# sc_v0.net
KiCad netlist of a schematic drawn in EAGLE
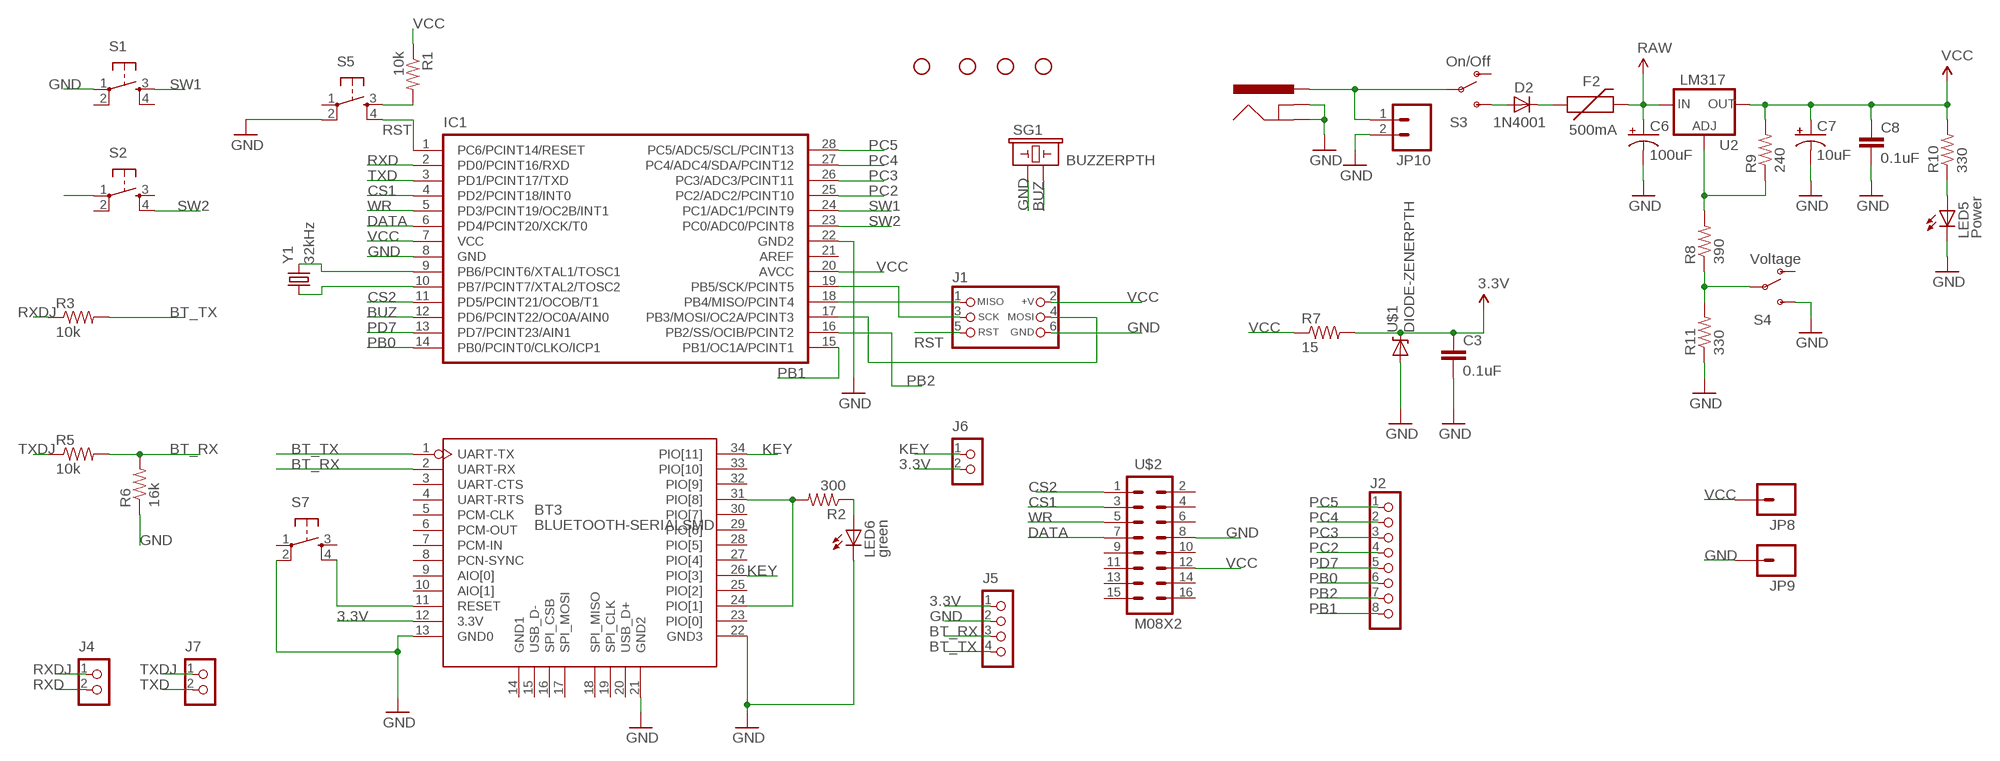
[diagram p0: schematic, sheet 1]

(export (version "E")
  (design (tool "Eeschema 10.0.6"))
  (components
    (comp (ref "BT3")
      (value "BLUETOOTH-SERIALSMD")
      (footprint "eagle-import:SERIAL_BLUETEETH")
      (libsource (lib "eagle-import") (part "BLUETOOTH-SERIALSMD"))
    )
    (comp (ref "C3")
      (value "0.1uF")
      (footprint "eagle-import:CAP-PTH-SMALL2")
      (libsource (lib "eagle-import") (part "CAPPTH2"))
    )
    (comp (ref "C6")
      (value "100uF")
      (footprint "eagle-import:CPOL-RADIAL-100UF-25V")
      (libsource (lib "eagle-import") (part "CAP_POLPTH1"))
    )
    (comp (ref "C7")
      (value "10uF")
      (footprint "eagle-import:CPOL-RADIAL-10UF-25V")
      (libsource (lib "eagle-import") (part "CAP_POLPTH2"))
    )
    (comp (ref "C8")
      (value "0.1uF")
      (footprint "eagle-import:CAP-PTH-SMALL2")
      (libsource (lib "eagle-import") (part "CAPPTH2"))
    )
    (comp (ref "D2")
      (value "1N4001")
      (footprint "eagle-import:DIODE-0.4")
      (libsource (lib "eagle-import") (part "DIODEPTH"))
    )
    (comp (ref "F2")
      (value "500mA")
      (footprint "eagle-import:PTC")
      (libsource (lib "eagle-import") (part "PTCPTH"))
    )
    (comp (ref "IC1")
      (value "IC_UC_ATMEGA328PDIL")
      (footprint "eagle-import:DIL28-N")
      (libsource (lib "eagle-import") (part "IC_UC_ATMEGA328PDIL"))
    )
    (comp (ref "J1")
      (value "CON_HEADER_PRG_AVR_ICSP")
      (footprint "eagle-import:HEADER_PRG_2X03")
      (libsource (lib "eagle-import") (part "CON_HEADER_PRG_AVR_ICSP"))
    )
    (comp (ref "J2")
      (value "CON_HEADER_1X08-PTH")
      (footprint "eagle-import:M1X8")
      (libsource (lib "eagle-import") (part "CON_HEADER_1X08-PTH"))
    )
    (comp (ref "J3")
      (value "POWER_JACKPTH")
      (footprint "eagle-import:POWER_JACK_PTH")
      (libsource (lib "eagle-import") (part "POWER_JACKPTH"))
    )
    (comp (ref "J4")
      (value "CON_HEADER_1X02-PTH")
      (footprint "eagle-import:M1X2")
      (libsource (lib "eagle-import") (part "CON_HEADER_1X02-PTH"))
    )
    (comp (ref "J5")
      (value "CON_HEADER_1X04")
      (footprint "eagle-import:M1X4")
      (libsource (lib "eagle-import") (part "CON_HEADER_1X04"))
    )
    (comp (ref "J6")
      (value "CON_HEADER_1X02-PTH")
      (footprint "eagle-import:M1X2")
      (libsource (lib "eagle-import") (part "CON_HEADER_1X02-PTH"))
    )
    (comp (ref "J7")
      (value "CON_HEADER_1X02-PTH")
      (footprint "eagle-import:M1X2")
      (libsource (lib "eagle-import") (part "CON_HEADER_1X02-PTH"))
    )
    (comp (ref "JP1")
      (value "STAND-OFF")
      (footprint "eagle-import:STAND-OFF")
      (libsource (lib "eagle-import") (part "STAND-OFF"))
    )
    (comp (ref "JP2")
      (value "STAND-OFF")
      (footprint "eagle-import:STAND-OFF")
      (libsource (lib "eagle-import") (part "STAND-OFF"))
    )
    (comp (ref "JP3")
      (value "STAND-OFF")
      (footprint "eagle-import:STAND-OFF")
      (libsource (lib "eagle-import") (part "STAND-OFF"))
    )
    (comp (ref "JP4")
      (value "STAND-OFF")
      (footprint "eagle-import:STAND-OFF")
      (libsource (lib "eagle-import") (part "STAND-OFF"))
    )
    (comp (ref "JP8")
      (value "M01PTH")
      (footprint "eagle-import:1X01")
      (libsource (lib "eagle-import") (part "M01PTH"))
    )
    (comp (ref "JP9")
      (value "M01PTH")
      (footprint "eagle-import:1X01")
      (libsource (lib "eagle-import") (part "M01PTH"))
    )
    (comp (ref "JP10")
      (value "M02PTH")
      (footprint "eagle-import:1X02")
      (libsource (lib "eagle-import") (part "M02PTH"))
    )
    (comp (ref "LED5")
      (value "Power")
      (footprint "eagle-import:LED5MM")
      (libsource (lib "eagle-import") (part "SparkFun-Nate_LED5MM"))
    )
    (comp (ref "LED6")
      (value "green")
      (footprint "eagle-import:LED3MM")
      (libsource (lib "eagle-import") (part "LED3MM"))
    )
    (comp (ref "R1")
      (value "10k")
      (footprint "eagle-import:AXIAL-0.3")
      (libsource (lib "eagle-import") (part "RESISTORAXIAL-0.3"))
    )
    (comp (ref "R2")
      (value "300")
      (footprint "eagle-import:AXIAL-0.3")
      (libsource (lib "eagle-import") (part "RESISTORAXIAL-0.3"))
    )
    (comp (ref "R3")
      (value "10k")
      (footprint "eagle-import:AXIAL-0.3")
      (libsource (lib "eagle-import") (part "RESISTORAXIAL-0.3"))
    )
    (comp (ref "R5")
      (value "10k")
      (footprint "eagle-import:AXIAL-0.3")
      (libsource (lib "eagle-import") (part "RESISTORAXIAL-0.3"))
    )
    (comp (ref "R6")
      (value "16k")
      (footprint "eagle-import:AXIAL-0.3")
      (libsource (lib "eagle-import") (part "RESISTORAXIAL-0.3"))
    )
    (comp (ref "R7")
      (value "15")
      (footprint "eagle-import:AXIAL-0.3")
      (libsource (lib "eagle-import") (part "RESISTORAXIAL-0.3"))
    )
    (comp (ref "R8")
      (value "390")
      (footprint "eagle-import:AXIAL-0.3")
      (libsource (lib "eagle-import") (part "RESISTORAXIAL-0.3"))
    )
    (comp (ref "R9")
      (value "240")
      (footprint "eagle-import:AXIAL-0.3")
      (libsource (lib "eagle-import") (part "RESISTORAXIAL-0.3"))
    )
    (comp (ref "R10")
      (value "330")
      (footprint "eagle-import:AXIAL-0.3")
      (libsource (lib "eagle-import") (part "RESISTORAXIAL-0.3"))
    )
    (comp (ref "R11")
      (value "330")
      (footprint "eagle-import:AXIAL-0.3")
      (libsource (lib "eagle-import") (part "RESISTORAXIAL-0.3"))
    )
    (comp (ref "S1")
      (value "TAC_SWITCHPTH")
      (footprint "eagle-import:TACTILE-PTH")
      (libsource (lib "eagle-import") (part "TAC_SWITCHPTH"))
    )
    (comp (ref "S2")
      (value "TAC_SWITCHPTH")
      (footprint "eagle-import:TACTILE-PTH")
      (libsource (lib "eagle-import") (part "TAC_SWITCHPTH"))
    )
    (comp (ref "S3")
      (value "On/Off")
      (footprint "eagle-import:SWITCH-SPST")
      (libsource (lib "eagle-import") (part "SWITCH-SPSTPTH"))
    )
    (comp (ref "S4")
      (value "Voltage")
      (footprint "eagle-import:SWITCH-SPST")
      (libsource (lib "eagle-import") (part "SWITCH-SPSTPTH"))
    )
    (comp (ref "S5")
      (value "TAC_SWITCHPTH")
      (footprint "eagle-import:TACTILE-PTH")
      (libsource (lib "eagle-import") (part "TAC_SWITCHPTH"))
    )
    (comp (ref "S7")
      (value "TAC_SWITCHPTH")
      (footprint "eagle-import:TACTILE-PTH")
      (libsource (lib "eagle-import") (part "TAC_SWITCHPTH"))
    )
    (comp (ref "SG1")
      (value "BUZZERPTH")
      (footprint "eagle-import:BUZZER-12MM")
      (libsource (lib "eagle-import") (part "BUZZERPTH"))
    )
    (comp (ref "U$1")
      (value "DIODE-ZENERPTH")
      (footprint "eagle-import:DIODE-ZENER")
      (libsource (lib "eagle-import") (part "DIODE-ZENERPTH"))
    )
    (comp (ref "U$2")
      (value "M08X2")
      (footprint "eagle-import:2X8")
      (libsource (lib "eagle-import") (part "M08X2"))
    )
    (comp (ref "U2")
      (value "LM317")
      (footprint "eagle-import:TO220-ADJ")
      (libsource (lib "eagle-import") (part "V_REG_317SINK"))
    )
    (comp (ref "Y1")
      (value "32kHz")
      (footprint "eagle-import:TC38H")
      (libsource (lib "eagle-import") (part "CRYSTALTC38H"))
    )
  )
  (nets
    (net (code "1") (name "/BT_RX") (class "Default")
      (node (ref "BT3") (pin "2") (pinfunction "UART-RX_2") (pintype "bidirectional"))
      (node (ref "J5") (pin "3") (pinfunction "3_3") (pintype "bidirectional"))
      (node (ref "R5") (pin "P$2") (pinfunction "2_P$2") (pintype "passive"))
      (node (ref "R6") (pin "P$2") (pinfunction "2_P$2") (pintype "passive"))
    )
    (net (code "2") (name "/BT_TX") (class "Default")
      (node (ref "BT3") (pin "1") (pinfunction "UART-TX_1") (pintype "bidirectional"))
      (node (ref "J5") (pin "4") (pinfunction "4_4") (pintype "bidirectional"))
      (node (ref "R3") (pin "P$2") (pinfunction "2_P$2") (pintype "passive"))
    )
    (net (code "3") (name "/BUZ") (class "Default")
      (node (ref "IC1") (pin "12") (pinfunction "PD6/PCINT22/OC0A/AIN0_12") (pintype "bidirectional"))
      (node (ref "SG1") (pin "-") (pinfunction "2_-") (pintype "passive"))
    )
    (net (code "4") (name "/CS1") (class "Default")
      (node (ref "IC1") (pin "4") (pinfunction "PD2/PCINT18/INT0_4") (pintype "bidirectional"))
      (node (ref "U$2") (pin "3") (pinfunction "3_3") (pintype "passive"))
    )
    (net (code "5") (name "/CS2") (class "Default")
      (node (ref "IC1") (pin "11") (pinfunction "PD5/PCINT21/OCOB/T1_11") (pintype "bidirectional"))
      (node (ref "U$2") (pin "1") (pinfunction "1_1") (pintype "passive"))
    )
    (net (code "6") (name "/DATA") (class "Default")
      (node (ref "IC1") (pin "6") (pinfunction "PD4/PCINT20/XCK/T0_6") (pintype "bidirectional"))
      (node (ref "U$2") (pin "7") (pinfunction "7_7") (pintype "passive"))
    )
    (net (code "7") (name "/KEY") (class "Default")
      (node (ref "BT3") (pin "26") (pinfunction "PIO[3]_26") (pintype "bidirectional"))
      (node (ref "BT3") (pin "34") (pinfunction "PIO[11]_34") (pintype "bidirectional"))
      (node (ref "J6") (pin "1") (pinfunction "1_1") (pintype "passive"))
    )
    (net (code "8") (name "/PB0") (class "Default")
      (node (ref "IC1") (pin "14") (pinfunction "PB0/PCINT0/CLKO/ICP1_14") (pintype "bidirectional"))
      (node (ref "J2") (pin "6") (pinfunction "6_6") (pintype "passive"))
    )
    (net (code "9") (name "/PB1") (class "Default")
      (node (ref "IC1") (pin "15") (pinfunction "PB1/OC1A/PCINT1_15") (pintype "bidirectional"))
      (node (ref "J2") (pin "8") (pinfunction "8_8") (pintype "passive"))
    )
    (net (code "10") (name "/PB2") (class "Default")
      (node (ref "IC1") (pin "16") (pinfunction "PB2/SS/OCIB/PCINT2_16") (pintype "bidirectional"))
      (node (ref "J2") (pin "7") (pinfunction "7_7") (pintype "passive"))
    )
    (net (code "11") (name "/PC2") (class "Default")
      (node (ref "IC1") (pin "25") (pinfunction "PC2/ADC2/PCINT10_25") (pintype "bidirectional"))
      (node (ref "J2") (pin "4") (pinfunction "4_4") (pintype "passive"))
    )
    (net (code "12") (name "/PC3") (class "Default")
      (node (ref "IC1") (pin "26") (pinfunction "PC3/ADC3/PCINT11_26") (pintype "bidirectional"))
      (node (ref "J2") (pin "3") (pinfunction "3_3") (pintype "passive"))
    )
    (net (code "13") (name "/PC4") (class "Default")
      (node (ref "IC1") (pin "27") (pinfunction "PC4/ADC4/SDA/PCINT12_27") (pintype "bidirectional"))
      (node (ref "J2") (pin "2") (pinfunction "2_2") (pintype "passive"))
    )
    (net (code "14") (name "/PC5") (class "Default")
      (node (ref "IC1") (pin "28") (pinfunction "PC5/ADC5/SCL/PCINT13_28") (pintype "bidirectional"))
      (node (ref "J2") (pin "1") (pinfunction "1_1") (pintype "passive"))
    )
    (net (code "15") (name "/PD7") (class "Default")
      (node (ref "IC1") (pin "13") (pinfunction "PD7/PCINT23/AIN1_13") (pintype "bidirectional"))
      (node (ref "J2") (pin "5") (pinfunction "5_5") (pintype "passive"))
    )
    (net (code "16") (name "/RST") (class "Default")
      (node (ref "IC1") (pin "1") (pinfunction "PC6/PCINT14/RESET_1") (pintype "bidirectional"))
      (node (ref "J1") (pin "5") (pinfunction "RST_5") (pintype "passive"))
      (node (ref "S5") (pin "4") (pinfunction "4_4") (pintype "passive"))
    )
    (net (code "17") (name "/RXD") (class "Default")
      (node (ref "IC1") (pin "2") (pinfunction "PD0/PCINT16/RXD_2") (pintype "bidirectional"))
      (node (ref "J4") (pin "2") (pinfunction "2_2") (pintype "passive"))
    )
    (net (code "18") (name "/RXDJ") (class "Default")
      (node (ref "J4") (pin "1") (pinfunction "1_1") (pintype "passive"))
      (node (ref "R3") (pin "P$1") (pinfunction "1_P$1") (pintype "passive"))
    )
    (net (code "19") (name "/SW1") (class "Default")
      (node (ref "IC1") (pin "24") (pinfunction "PC1/ADC1/PCINT9_24") (pintype "bidirectional"))
      (node (ref "S1") (pin "3") (pinfunction "3_3") (pintype "passive"))
    )
    (net (code "20") (name "/SW2") (class "Default")
      (node (ref "IC1") (pin "23") (pinfunction "PC0/ADC0/PCINT8_23") (pintype "bidirectional"))
      (node (ref "S2") (pin "4") (pinfunction "4_4") (pintype "passive"))
    )
    (net (code "21") (name "/TXD") (class "Default")
      (node (ref "IC1") (pin "3") (pinfunction "PD1/PCINT17/TXD_3") (pintype "bidirectional"))
      (node (ref "J7") (pin "2") (pinfunction "2_2") (pintype "passive"))
    )
    (net (code "22") (name "/TXDJ") (class "Default")
      (node (ref "J7") (pin "1") (pinfunction "1_1") (pintype "passive"))
      (node (ref "R5") (pin "P$1") (pinfunction "1_P$1") (pintype "passive"))
    )
    (net (code "23") (name "/WR") (class "Default")
      (node (ref "IC1") (pin "5") (pinfunction "PD3/PCINT19/OC2B/INT1_5") (pintype "bidirectional"))
      (node (ref "U$2") (pin "5") (pinfunction "5_5") (pintype "passive"))
    )
    (net (code "24") (name "3.3V") (class "Default")
      (node (ref "BT3") (pin "12") (pinfunction "3.3V_12") (pintype "bidirectional"))
      (node (ref "C3") (pin "1") (pinfunction "1_1") (pintype "passive"))
      (node (ref "J5") (pin "1") (pinfunction "1_1") (pintype "bidirectional"))
      (node (ref "J6") (pin "2") (pinfunction "2_2") (pintype "passive"))
      (node (ref "R7") (pin "P$2") (pinfunction "2_P$2") (pintype "passive"))
      (node (ref "U$1") (pin "P$1") (pinfunction "C_P$1") (pintype "passive"))
    )
    (net (code "25") (name "GND") (class "Default")
      (node (ref "BT3") (pin "13") (pinfunction "GND0_13") (pintype "bidirectional"))
      (node (ref "BT3") (pin "21") (pinfunction "GND2_21") (pintype "bidirectional"))
      (node (ref "BT3") (pin "22") (pinfunction "GND3_22") (pintype "bidirectional"))
      (node (ref "C3") (pin "2") (pinfunction "2_2") (pintype "passive"))
      (node (ref "C6") (pin "2") (pinfunction "-_2") (pintype "passive"))
      (node (ref "C7") (pin "2") (pinfunction "-_2") (pintype "passive"))
      (node (ref "C8") (pin "2") (pinfunction "2_2") (pintype "passive"))
      (node (ref "IC1") (pin "22") (pinfunction "GND2_22") (pintype "bidirectional"))
      (node (ref "IC1") (pin "8") (pinfunction "GND_8") (pintype "bidirectional"))
      (node (ref "J1") (pin "6") (pinfunction "GND_6") (pintype "passive"))
      (node (ref "J3") (pin "GND") (pinfunction "GND_GND") (pintype "bidirectional"))
      (node (ref "J3") (pin "GNDBREAK") (pinfunction "GNDBREAK_GNDBREAK") (pintype "bidirectional"))
      (node (ref "J5") (pin "2") (pinfunction "2_2") (pintype "bidirectional"))
      (node (ref "JP10") (pin "2") (pinfunction "2_2") (pintype "passive"))
      (node (ref "JP9") (pin "1") (pinfunction "1_1") (pintype "passive"))
      (node (ref "LED5") (pin "K") (pinfunction "C_K") (pintype "passive"))
      (node (ref "LED6") (pin "K") (pinfunction "C_K") (pintype "passive"))
      (node (ref "R11") (pin "P$1") (pinfunction "1_P$1") (pintype "passive"))
      (node (ref "R6") (pin "P$1") (pinfunction "1_P$1") (pintype "passive"))
      (node (ref "S1") (pin "1") (pinfunction "1_1") (pintype "passive"))
      (node (ref "S2") (pin "1") (pinfunction "1_1") (pintype "passive"))
      (node (ref "S4") (pin "3") (pinfunction "S_3") (pintype "passive"))
      (node (ref "S5") (pin "2") (pinfunction "2_2") (pintype "passive"))
      (node (ref "S7") (pin "2") (pinfunction "2_2") (pintype "passive"))
      (node (ref "SG1") (pin "+") (pinfunction "1_+") (pintype "passive"))
      (node (ref "U$1") (pin "P$2") (pinfunction "A_P$2") (pintype "passive"))
      (node (ref "U$2") (pin "8") (pinfunction "8_8") (pintype "passive"))
    )
    (net (code "26") (name "Net-(BT3-PIO[1])") (class "Default")
      (node (ref "BT3") (pin "24") (pinfunction "PIO[1]_24") (pintype "bidirectional"))
      (node (ref "BT3") (pin "31") (pinfunction "PIO[8]_31") (pintype "bidirectional"))
      (node (ref "R2") (pin "P$2") (pinfunction "2_P$2") (pintype "passive"))
    )
    (net (code "27") (name "Net-(BT3-RESET)") (class "Default")
      (node (ref "BT3") (pin "11") (pinfunction "RESET_11") (pintype "bidirectional"))
      (node (ref "S7") (pin "4") (pinfunction "4_4") (pintype "passive"))
    )
    (net (code "28") (name "Net-(F2-1)") (class "Default")
      (node (ref "D2") (pin "C") (pinfunction "C_C") (pintype "passive"))
      (node (ref "F2") (pin "P$1") (pinfunction "1_P$1") (pintype "bidirectional"))
    )
    (net (code "29") (name "Net-(IC1-PB3{slash}MOSI{slash}OC2A{slash}PCINT3)") (class "Default")
      (node (ref "IC1") (pin "17") (pinfunction "PB3/MOSI/OC2A/PCINT3_17") (pintype "bidirectional"))
      (node (ref "J1") (pin "4") (pinfunction "MOSI_4") (pintype "passive"))
    )
    (net (code "30") (name "Net-(IC1-PB4{slash}MISO{slash}PCINT4)") (class "Default")
      (node (ref "IC1") (pin "18") (pinfunction "PB4/MISO/PCINT4_18") (pintype "bidirectional"))
      (node (ref "J1") (pin "1") (pinfunction "MISO_1") (pintype "passive"))
    )
    (net (code "31") (name "Net-(IC1-PB5{slash}SCK{slash}PCINT5)") (class "Default")
      (node (ref "IC1") (pin "19") (pinfunction "PB5/SCK/PCINT5_19") (pintype "bidirectional"))
      (node (ref "J1") (pin "3") (pinfunction "SCK_3") (pintype "passive"))
    )
    (net (code "32") (name "Net-(IC1-PB6{slash}PCINT6{slash}XTAL1{slash}TOSC1)") (class "Default")
      (node (ref "IC1") (pin "9") (pinfunction "PB6/PCINT6/XTAL1/TOSC1_9") (pintype "bidirectional"))
      (node (ref "Y1") (pin "2") (pinfunction "2_2") (pintype "passive"))
    )
    (net (code "33") (name "Net-(IC1-PB7{slash}PCINT7{slash}XTAL2{slash}TOSC2)") (class "Default")
      (node (ref "IC1") (pin "10") (pinfunction "PB7/PCINT7/XTAL2/TOSC2_10") (pintype "bidirectional"))
      (node (ref "Y1") (pin "1") (pinfunction "1_1") (pintype "passive"))
    )
    (net (code "34") (name "Net-(R1-2)") (class "Default")
      (node (ref "R1") (pin "P$2") (pinfunction "2_P$2") (pintype "passive"))
      (node (ref "S5") (pin "3") (pinfunction "3_3") (pintype "passive"))
    )
    (net (code "35") (name "Net-(R2-1)") (class "Default")
      (node (ref "LED6") (pin "A") (pinfunction "A_A") (pintype "passive"))
      (node (ref "R2") (pin "P$1") (pinfunction "1_P$1") (pintype "passive"))
    )
    (net (code "36") (name "Net-(R8-2)") (class "Default")
      (node (ref "R8") (pin "P$2") (pinfunction "2_P$2") (pintype "passive"))
      (node (ref "R9") (pin "P$1") (pinfunction "1_P$1") (pintype "passive"))
      (node (ref "U2") (pin "ADJ") (pinfunction "ADJ_ADJ") (pintype "input"))
    )
    (net (code "37") (name "Net-(R10-1)") (class "Default")
      (node (ref "LED5") (pin "A") (pinfunction "A_A") (pintype "passive"))
      (node (ref "R10") (pin "P$1") (pinfunction "1_P$1") (pintype "passive"))
    )
    (net (code "38") (name "Net-(R11-2)") (class "Default")
      (node (ref "R11") (pin "P$2") (pinfunction "2_P$2") (pintype "passive"))
      (node (ref "R8") (pin "P$1") (pinfunction "1_P$1") (pintype "passive"))
      (node (ref "S4") (pin "2") (pinfunction "P_2") (pintype "passive"))
    )
    (net (code "39") (name "Net-(S3-P)") (class "Default")
      (node (ref "J3") (pin "PWR") (pinfunction "PWR_PWR") (pintype "bidirectional"))
      (node (ref "JP10") (pin "1") (pinfunction "1_1") (pintype "passive"))
      (node (ref "S3") (pin "2") (pinfunction "P_2") (pintype "passive"))
    )
    (net (code "40") (name "Net-(S3-S)") (class "Default")
      (node (ref "D2") (pin "A") (pinfunction "A_A") (pintype "passive"))
      (node (ref "S3") (pin "3") (pinfunction "S_3") (pintype "passive"))
    )
    (net (code "41") (name "RAW") (class "Default")
      (node (ref "C6") (pin "1") (pinfunction "+_1") (pintype "passive"))
      (node (ref "F2") (pin "P$2") (pinfunction "2_P$2") (pintype "bidirectional"))
      (node (ref "U2") (pin "IN") (pinfunction "IN_IN") (pintype "input"))
    )
    (net (code "42") (name "VCC") (class "Default")
      (node (ref "C7") (pin "1") (pinfunction "+_1") (pintype "passive"))
      (node (ref "C8") (pin "1") (pinfunction "1_1") (pintype "passive"))
      (node (ref "IC1") (pin "20") (pinfunction "AVCC_20") (pintype "bidirectional"))
      (node (ref "IC1") (pin "7") (pinfunction "VCC_7") (pintype "bidirectional"))
      (node (ref "J1") (pin "2") (pinfunction "+V_2") (pintype "passive"))
      (node (ref "JP8") (pin "1") (pinfunction "1_1") (pintype "passive"))
      (node (ref "R1") (pin "P$1") (pinfunction "1_P$1") (pintype "passive"))
      (node (ref "R10") (pin "P$2") (pinfunction "2_P$2") (pintype "passive"))
      (node (ref "R7") (pin "P$1") (pinfunction "1_P$1") (pintype "passive"))
      (node (ref "R9") (pin "P$2") (pinfunction "2_P$2") (pintype "passive"))
      (node (ref "U$2") (pin "12") (pinfunction "12_12") (pintype "passive"))
      (node (ref "U2") (pin "OUT") (pinfunction "OUT_OUT") (pintype "output"))
    )
    (net (code "43") (name "unconnected-(BT3-AIO[0]-Pad9)") (class "Default")
      (node (ref "BT3") (pin "9") (pinfunction "AIO[0]_9") (pintype "bidirectional"))
    )
    (net (code "44") (name "unconnected-(BT3-AIO[1]-Pad10)") (class "Default")
      (node (ref "BT3") (pin "10") (pinfunction "AIO[1]_10") (pintype "bidirectional"))
    )
    (net (code "45") (name "unconnected-(BT3-GND1-Pad14)") (class "Default")
      (node (ref "BT3") (pin "14") (pinfunction "GND1_14") (pintype "bidirectional"))
    )
    (net (code "46") (name "unconnected-(BT3-PCM-CLK-Pad5)") (class "Default")
      (node (ref "BT3") (pin "5") (pinfunction "PCM-CLK_5") (pintype "bidirectional"))
    )
    (net (code "47") (name "unconnected-(BT3-PCM-IN-Pad7)") (class "Default")
      (node (ref "BT3") (pin "7") (pinfunction "PCM-IN_7") (pintype "bidirectional"))
    )
    (net (code "48") (name "unconnected-(BT3-PCM-OUT-Pad6)") (class "Default")
      (node (ref "BT3") (pin "6") (pinfunction "PCM-OUT_6") (pintype "bidirectional"))
    )
    (net (code "49") (name "unconnected-(BT3-PCN-SYNC-Pad8)") (class "Default")
      (node (ref "BT3") (pin "8") (pinfunction "PCN-SYNC_8") (pintype "bidirectional"))
    )
    (net (code "50") (name "unconnected-(BT3-PIO[0]-Pad23)") (class "Default")
      (node (ref "BT3") (pin "23") (pinfunction "PIO[0]_23") (pintype "bidirectional"))
    )
    (net (code "51") (name "unconnected-(BT3-PIO[2]-Pad25)") (class "Default")
      (node (ref "BT3") (pin "25") (pinfunction "PIO[2]_25") (pintype "bidirectional"))
    )
    (net (code "52") (name "unconnected-(BT3-PIO[4]-Pad27)") (class "Default")
      (node (ref "BT3") (pin "27") (pinfunction "PIO[4]_27") (pintype "bidirectional"))
    )
    (net (code "53") (name "unconnected-(BT3-PIO[5]-Pad28)") (class "Default")
      (node (ref "BT3") (pin "28") (pinfunction "PIO[5]_28") (pintype "bidirectional"))
    )
    (net (code "54") (name "unconnected-(BT3-PIO[6]-Pad29)") (class "Default")
      (node (ref "BT3") (pin "29") (pinfunction "PIO[6]_29") (pintype "bidirectional"))
    )
    (net (code "55") (name "unconnected-(BT3-PIO[7]-Pad30)") (class "Default")
      (node (ref "BT3") (pin "30") (pinfunction "PIO[7]_30") (pintype "bidirectional"))
    )
    (net (code "56") (name "unconnected-(BT3-PIO[9]-Pad32)") (class "Default")
      (node (ref "BT3") (pin "32") (pinfunction "PIO[9]_32") (pintype "bidirectional"))
    )
    (net (code "57") (name "unconnected-(BT3-PIO[10]-Pad33)") (class "Default")
      (node (ref "BT3") (pin "33") (pinfunction "PIO[10]_33") (pintype "bidirectional"))
    )
    (net (code "58") (name "unconnected-(BT3-SPI_CLK-Pad19)") (class "Default")
      (node (ref "BT3") (pin "19") (pinfunction "SPI_CLK_19") (pintype "bidirectional"))
    )
    (net (code "59") (name "unconnected-(BT3-SPI_CSB-Pad16)") (class "Default")
      (node (ref "BT3") (pin "16") (pinfunction "SPI_CSB_16") (pintype "bidirectional"))
    )
    (net (code "60") (name "unconnected-(BT3-SPI_MISO-Pad18)") (class "Default")
      (node (ref "BT3") (pin "18") (pinfunction "SPI_MISO_18") (pintype "bidirectional"))
    )
    (net (code "61") (name "unconnected-(BT3-SPI_MOSI-Pad17)") (class "Default")
      (node (ref "BT3") (pin "17") (pinfunction "SPI_MOSI_17") (pintype "bidirectional"))
    )
    (net (code "62") (name "unconnected-(BT3-UART-CTS-Pad3)") (class "Default")
      (node (ref "BT3") (pin "3") (pinfunction "UART-CTS_3") (pintype "bidirectional"))
    )
    (net (code "63") (name "unconnected-(BT3-UART-RTS-Pad4)") (class "Default")
      (node (ref "BT3") (pin "4") (pinfunction "UART-RTS_4") (pintype "bidirectional"))
    )
    (net (code "64") (name "unconnected-(BT3-USB_D+-Pad20)") (class "Default")
      (node (ref "BT3") (pin "20") (pinfunction "USB_D+_20") (pintype "bidirectional"))
    )
    (net (code "65") (name "unconnected-(BT3-USB_D--Pad15)") (class "Default")
      (node (ref "BT3") (pin "15") (pinfunction "USB_D-_15") (pintype "bidirectional"))
    )
    (net (code "66") (name "unconnected-(IC1-AREF-Pad21)") (class "Default")
      (node (ref "IC1") (pin "21") (pinfunction "AREF_21") (pintype "bidirectional"))
    )
    (net (code "67") (name "unconnected-(S1-Pad2)") (class "Default")
      (node (ref "S1") (pin "2") (pinfunction "2_2") (pintype "passive"))
    )
    (net (code "68") (name "unconnected-(S1-Pad4)") (class "Default")
      (node (ref "S1") (pin "4") (pinfunction "4_4") (pintype "passive"))
    )
    (net (code "69") (name "unconnected-(S2-Pad2)") (class "Default")
      (node (ref "S2") (pin "2") (pinfunction "2_2") (pintype "passive"))
    )
    (net (code "70") (name "unconnected-(S2-Pad3)") (class "Default")
      (node (ref "S2") (pin "3") (pinfunction "3_3") (pintype "passive"))
    )
    (net (code "71") (name "unconnected-(S3-O-Pad1)") (class "Default")
      (node (ref "S3") (pin "1") (pinfunction "O_1") (pintype "passive"))
    )
    (net (code "72") (name "unconnected-(S4-O-Pad1)") (class "Default")
      (node (ref "S4") (pin "1") (pinfunction "O_1") (pintype "passive"))
    )
    (net (code "73") (name "unconnected-(S5-Pad1)") (class "Default")
      (node (ref "S5") (pin "1") (pinfunction "1_1") (pintype "passive"))
    )
    (net (code "74") (name "unconnected-(S7-Pad1)") (class "Default")
      (node (ref "S7") (pin "1") (pinfunction "1_1") (pintype "passive"))
    )
    (net (code "75") (name "unconnected-(S7-Pad3)") (class "Default")
      (node (ref "S7") (pin "3") (pinfunction "3_3") (pintype "passive"))
    )
    (net (code "76") (name "unconnected-(U$2-Pad2)") (class "Default")
      (node (ref "U$2") (pin "2") (pinfunction "2_2") (pintype "passive"))
    )
    (net (code "77") (name "unconnected-(U$2-Pad4)") (class "Default")
      (node (ref "U$2") (pin "4") (pinfunction "4_4") (pintype "passive"))
    )
    (net (code "78") (name "unconnected-(U$2-Pad6)") (class "Default")
      (node (ref "U$2") (pin "6") (pinfunction "6_6") (pintype "passive"))
    )
    (net (code "79") (name "unconnected-(U$2-Pad9)") (class "Default")
      (node (ref "U$2") (pin "9") (pinfunction "9_9") (pintype "passive"))
    )
    (net (code "80") (name "unconnected-(U$2-Pad10)") (class "Default")
      (node (ref "U$2") (pin "10") (pinfunction "10_10") (pintype "passive"))
    )
    (net (code "81") (name "unconnected-(U$2-Pad11)") (class "Default")
      (node (ref "U$2") (pin "11") (pinfunction "11_11") (pintype "passive"))
    )
    (net (code "82") (name "unconnected-(U$2-Pad13)") (class "Default")
      (node (ref "U$2") (pin "13") (pinfunction "13_13") (pintype "passive"))
    )
    (net (code "83") (name "unconnected-(U$2-Pad14)") (class "Default")
      (node (ref "U$2") (pin "14") (pinfunction "14_14") (pintype "passive"))
    )
    (net (code "84") (name "unconnected-(U$2-Pad15)") (class "Default")
      (node (ref "U$2") (pin "15") (pinfunction "15_15") (pintype "passive"))
    )
    (net (code "85") (name "unconnected-(U$2-Pad16)") (class "Default")
      (node (ref "U$2") (pin "16") (pinfunction "16_16") (pintype "passive"))
    )
  )
)
